# Flex.net
KiCad netlist of a schematic drawn in Altium Designer
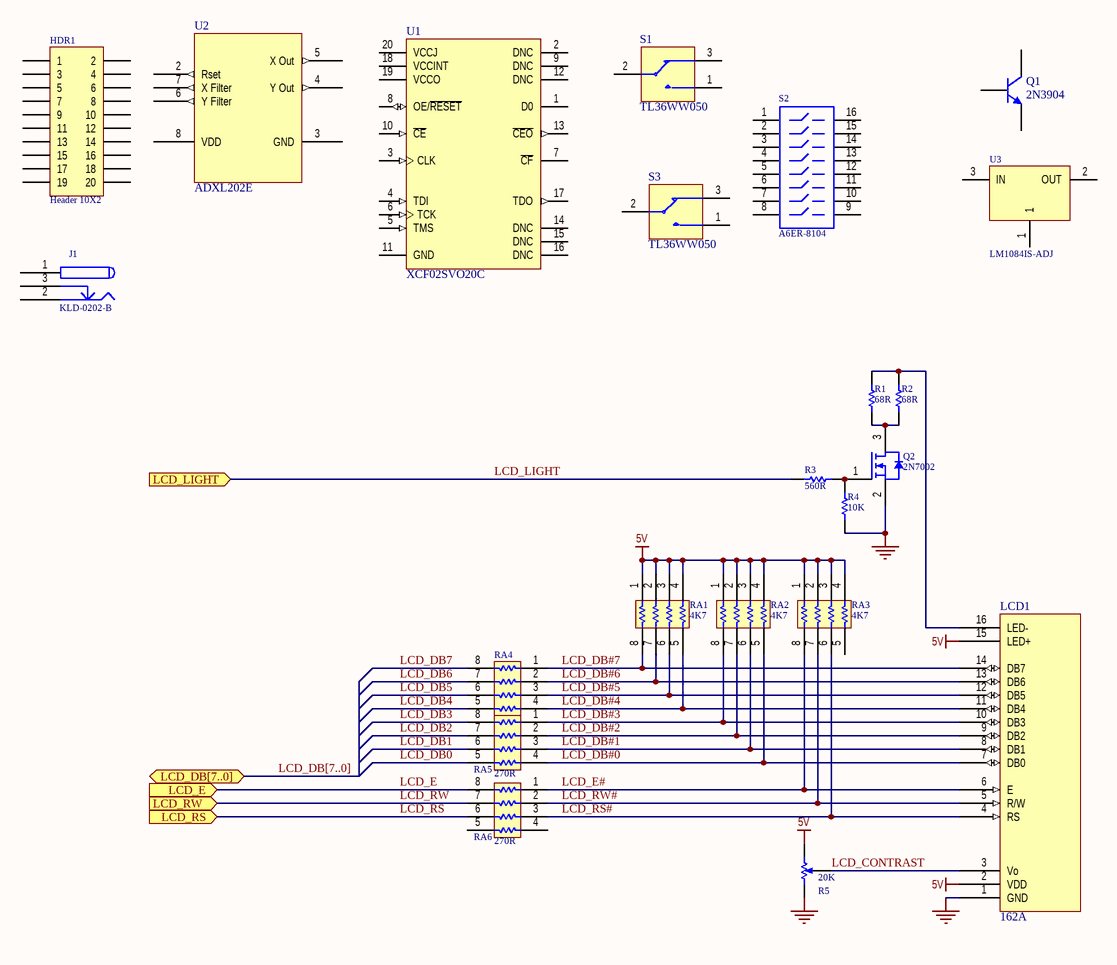
[diagram p0: Flex.SchDoc]

(export (version "E")
  (design (tool "Eeschema 10.0.6"))
  (components
    (comp (ref "HDR1")
      (value "Header 10X2")
      (footprint "HDR2X10")
      (description "Header, 10-Pin, Dual row")
      (libsource (lib "Flex") (part "Header 10X2"))
    )
    (comp (ref "J1")
      (value "KLD-0202-B")
      (footprint "KLD-0202")
      (description "Low Voltage Power Supply Connector")
      (fields (field (name "MANUFACTURER") "Kycon"))
      (libsource (lib "Flex") (part "KLD-0202-B"))
    )
    (comp (ref "LCD1")
      (value "162A")
      (footprint "162A")
      (description "16 char * 2 line LCD character display with b/light")
      (libsource (lib "Flex") (part "162A"))
    )
    (comp (ref "Q1")
      (value "2N3904")
      (footprint "TO-92A")
      (description "NPN General Purpose Amplifier")
      (fields (field (name "PUBLISHER") "Altium Limited"))
      (libsource (lib "Miscellaneous Devices") (part "2N3904"))
    )
    (comp (ref "Q2")
      (value "2N7002")
      (footprint "SO-G3")
      (description "N Channel Mosfet")
      (libsource (lib "Flex") (part "2N7002"))
    )
    (comp (ref "R1")
      (value "68R")
      (footprint "CC2012-0805")
      (description "Resistor")
      (libsource (lib "Flex") (part "RES_2"))
    )
    (comp (ref "R2")
      (value "68R")
      (footprint "CC2012-0805")
      (description "Resistor")
      (libsource (lib "Flex") (part "RES_2"))
    )
    (comp (ref "R3")
      (value "560R")
      (footprint "CC2012-0805")
      (description "Resistor")
      (libsource (lib "SpiritLevel_2E") (part "RES"))
    )
    (comp (ref "R4")
      (value "10K")
      (footprint "CR2012-0805")
      (description "Resistor")
      (libsource (lib "Flex") (part "RES"))
    )
    (comp (ref "R5")
      (value "20K")
      (footprint "POT4MM-2")
      (description "Square Trimming Potentiometer")
      (libsource (lib "Flex") (part "RPot SM"))
    )
    (comp (ref "RA1")
      (value "4K7")
      (footprint "MNR34T")
      (description "3216x4 Resistor Array")
      (libsource (lib "Flex") (part "MNR34"))
    )
    (comp (ref "RA2")
      (value "4K7")
      (footprint "MNR34T")
      (description "3216x4 Resistor Array")
      (libsource (lib "Flex") (part "MNR34"))
    )
    (comp (ref "RA3")
      (value "4K7")
      (footprint "MNR34T")
      (description "3216x4 Resistor Array")
      (libsource (lib "Flex") (part "MNR34"))
    )
    (comp (ref "RA4")
      (value "270R")
      (footprint "MNR34")
      (description "3216x4 Resistor Array")
      (libsource (lib "") (part "MNR34_1"))
    )
    (comp (ref "RA5")
      (value "270R")
      (footprint "MNR34")
      (description "3216x4 Resistor Array")
      (libsource (lib "") (part "MNR34_1"))
    )
    (comp (ref "RA6")
      (value "270R")
      (footprint "MNR34")
      (description "3216x4 Resistor Array")
      (libsource (lib "") (part "MNR34_1"))
    )
    (comp (ref "S1")
      (value "TL36WW050")
      (footprint "PCB_SWITCH")
      (description "SPDT Subminiature Toggle Switch")
      (libsource (lib "Flex") (part "PCB_MOUNT_SWITCH"))
    )
    (comp (ref "S2")
      (value "A6ER-8104")
      (footprint "DIP-16-KEY")
      (description "DIP Switch Side actuator long liver Piano Key")
      (libsource (lib "Flex") (part "A6ER-8104"))
    )
    (comp (ref "S3")
      (value "TL36WW050")
      (footprint "PCB_SWITCH")
      (description "SPDT Subminiature Toggle Switch")
      (libsource (lib "Flex") (part "PCB_MOUNT_SWITCH"))
    )
    (comp (ref "U1") (value "XCF02SVO20C") (footprint "VO20") (libsource (lib "Flex") (part "XCF02SVO20C")))
    (comp (ref "U2")
      (value "ADXL202E")
      (footprint "E-8")
      (description "Accelerometer with Digital Output")
      (libsource (lib "Flex") (part "ADXL202E"))
    )
    (comp (ref "U3")
      (value "LM1084IS-ADJ")
      (footprint "TO-263")
      (description "5A Low Dropout Possitive Regulators")
      (libsource (lib "Flex") (part "LM1084IS-ADJ"))
    )
  )
  (nets
    (net (code "1") (name "/LCD_CONTRAST") (class "Default")
      (node (ref "LCD1") (pin "3") (pinfunction "Vo_3") (pintype "tri_state"))
      (node (ref "R5") (pin "W") (pintype "passive"))
    )
    (net (code "2") (name "/LCD_DB#0") (class "Default")
      (node (ref "LCD1") (pin "7") (pinfunction "DB0_7") (pintype "bidirectional"))
      (node (ref "RA2") (pin "5") (pintype "passive"))
      (node (ref "RA5") (pin "4") (pintype "passive"))
    )
    (net (code "3") (name "/LCD_DB#1") (class "Default")
      (node (ref "LCD1") (pin "8") (pinfunction "DB1_8") (pintype "bidirectional"))
      (node (ref "RA2") (pin "6") (pintype "passive"))
      (node (ref "RA5") (pin "3") (pintype "passive"))
    )
    (net (code "4") (name "/LCD_DB#2") (class "Default")
      (node (ref "LCD1") (pin "9") (pinfunction "DB2_9") (pintype "bidirectional"))
      (node (ref "RA2") (pin "7") (pintype "passive"))
      (node (ref "RA5") (pin "2") (pintype "passive"))
    )
    (net (code "5") (name "/LCD_DB#3") (class "Default")
      (node (ref "LCD1") (pin "10") (pinfunction "DB3_10") (pintype "bidirectional"))
      (node (ref "RA2") (pin "8") (pintype "passive"))
      (node (ref "RA5") (pin "1") (pintype "passive"))
    )
    (net (code "6") (name "/LCD_DB#4") (class "Default")
      (node (ref "LCD1") (pin "11") (pinfunction "DB4_11") (pintype "bidirectional"))
      (node (ref "RA1") (pin "5") (pintype "passive"))
      (node (ref "RA4") (pin "4") (pintype "passive"))
    )
    (net (code "7") (name "/LCD_DB#5") (class "Default")
      (node (ref "LCD1") (pin "12") (pinfunction "DB5_12") (pintype "bidirectional"))
      (node (ref "RA1") (pin "6") (pintype "passive"))
      (node (ref "RA4") (pin "3") (pintype "passive"))
    )
    (net (code "8") (name "/LCD_DB#6") (class "Default")
      (node (ref "LCD1") (pin "13") (pinfunction "DB6_13") (pintype "bidirectional"))
      (node (ref "RA1") (pin "7") (pintype "passive"))
      (node (ref "RA4") (pin "2") (pintype "passive"))
    )
    (net (code "9") (name "/LCD_DB#7") (class "Default")
      (node (ref "LCD1") (pin "14") (pinfunction "DB7_14") (pintype "bidirectional"))
      (node (ref "RA1") (pin "8") (pintype "passive"))
      (node (ref "RA4") (pin "1") (pintype "passive"))
    )
    (net (code "10") (name "/LCD_DB0") (class "Default") (node (ref "RA5") (pin "5") (pintype "passive")))
    (net (code "11") (name "/LCD_DB1") (class "Default") (node (ref "RA5") (pin "6") (pintype "passive")))
    (net (code "12") (name "/LCD_DB2") (class "Default") (node (ref "RA5") (pin "7") (pintype "passive")))
    (net (code "13") (name "/LCD_DB3") (class "Default") (node (ref "RA5") (pin "8") (pintype "passive")))
    (net (code "14") (name "/LCD_DB4") (class "Default") (node (ref "RA4") (pin "5") (pintype "passive")))
    (net (code "15") (name "/LCD_DB5") (class "Default") (node (ref "RA4") (pin "6") (pintype "passive")))
    (net (code "16") (name "/LCD_DB6") (class "Default") (node (ref "RA4") (pin "7") (pintype "passive")))
    (net (code "17") (name "/LCD_DB7") (class "Default") (node (ref "RA4") (pin "8") (pintype "passive")))
    (net (code "19") (name "/LCD_E") (class "Default") (node (ref "RA6") (pin "8") (pintype "passive")))
    (net (code "20") (name "/LCD_E#") (class "Default")
      (node (ref "LCD1") (pin "6") (pinfunction "E_6") (pintype "input"))
      (node (ref "RA3") (pin "8") (pintype "passive"))
      (node (ref "RA6") (pin "1") (pintype "passive"))
    )
    (net (code "21") (name "/LCD_LIGHT") (class "Default")
      (node (ref "R3") (pin "1") (pinfunction "1_1") (pintype "passive"))
    )
    (net (code "22") (name "/LCD_RS") (class "Default") (node (ref "RA6") (pin "6") (pintype "passive")))
    (net (code "23") (name "/LCD_RS#") (class "Default")
      (node (ref "LCD1") (pin "4") (pinfunction "RS_4") (pintype "input"))
      (node (ref "RA3") (pin "6") (pintype "passive"))
      (node (ref "RA6") (pin "3") (pintype "passive"))
    )
    (net (code "24") (name "/LCD_RW") (class "Default") (node (ref "RA6") (pin "7") (pintype "passive")))
    (net (code "25") (name "/LCD_RW#") (class "Default")
      (node (ref "LCD1") (pin "5") (pinfunction "R/W_5") (pintype "input"))
      (node (ref "RA3") (pin "7") (pintype "passive"))
      (node (ref "RA6") (pin "2") (pintype "passive"))
    )
    (net (code "26") (name "5V") (class "Default")
      (node (ref "LCD1") (pin "15") (pinfunction "LED+_15") (pintype "power_in"))
      (node (ref "LCD1") (pin "2") (pinfunction "VDD_2") (pintype "power_in"))
      (node (ref "R5") (pin "CW") (pinfunction "+_CW") (pintype "passive"))
      (node (ref "RA1") (pin "1") (pintype "passive"))
      (node (ref "RA1") (pin "2") (pintype "passive"))
      (node (ref "RA1") (pin "3") (pintype "passive"))
      (node (ref "RA1") (pin "4") (pintype "passive"))
      (node (ref "RA2") (pin "1") (pintype "passive"))
      (node (ref "RA2") (pin "2") (pintype "passive"))
      (node (ref "RA2") (pin "3") (pintype "passive"))
      (node (ref "RA2") (pin "4") (pintype "passive"))
      (node (ref "RA3") (pin "1") (pintype "passive"))
      (node (ref "RA3") (pin "2") (pintype "passive"))
      (node (ref "RA3") (pin "3") (pintype "passive"))
      (node (ref "RA3") (pin "4") (pintype "passive"))
    )
    (net (code "27") (name "GND") (class "Default")
      (node (ref "LCD1") (pin "1") (pinfunction "GND_1") (pintype "power_in"))
      (node (ref "Q2") (pin "2") (pintype "passive"))
      (node (ref "R4") (pin "1") (pinfunction "1_1") (pintype "passive"))
      (node (ref "R5") (pin "CCW") (pinfunction "-_CCW") (pintype "passive"))
    )
    (net (code "28") (name "Net-(LCD1-LED-)") (class "Default")
      (node (ref "LCD1") (pin "16") (pinfunction "LED-_16") (pintype "power_in"))
      (node (ref "R1") (pin "1") (pinfunction "1_1") (pintype "passive"))
      (node (ref "R2") (pin "1") (pinfunction "1_1") (pintype "passive"))
    )
    (net (code "29") (name "Net-(Q2-Pad1)") (class "Default")
      (node (ref "Q2") (pin "1") (pintype "passive"))
      (node (ref "R3") (pin "2") (pinfunction "2_2") (pintype "passive"))
      (node (ref "R4") (pin "2") (pinfunction "2_2") (pintype "passive"))
    )
    (net (code "30") (name "Net-(Q2-Pad3)") (class "Default")
      (node (ref "Q2") (pin "3") (pintype "passive"))
      (node (ref "R1") (pin "2") (pinfunction "2_2") (pintype "passive"))
      (node (ref "R2") (pin "2") (pinfunction "2_2") (pintype "passive"))
    )
    (net (code "31") (name "unconnected-(HDR1-Pad1)") (class "Default")
      (node (ref "HDR1") (pin "1") (pinfunction "1_1") (pintype "passive"))
    )
    (net (code "32") (name "unconnected-(HDR1-Pad2)") (class "Default")
      (node (ref "HDR1") (pin "2") (pinfunction "2_2") (pintype "passive"))
    )
    (net (code "33") (name "unconnected-(HDR1-Pad3)") (class "Default")
      (node (ref "HDR1") (pin "3") (pinfunction "3_3") (pintype "passive"))
    )
    (net (code "34") (name "unconnected-(HDR1-Pad4)") (class "Default")
      (node (ref "HDR1") (pin "4") (pinfunction "4_4") (pintype "passive"))
    )
    (net (code "35") (name "unconnected-(HDR1-Pad5)") (class "Default")
      (node (ref "HDR1") (pin "5") (pinfunction "5_5") (pintype "passive"))
    )
    (net (code "36") (name "unconnected-(HDR1-Pad6)") (class "Default")
      (node (ref "HDR1") (pin "6") (pinfunction "6_6") (pintype "passive"))
    )
    (net (code "37") (name "unconnected-(HDR1-Pad7)") (class "Default")
      (node (ref "HDR1") (pin "7") (pinfunction "7_7") (pintype "passive"))
    )
    (net (code "38") (name "unconnected-(HDR1-Pad8)") (class "Default")
      (node (ref "HDR1") (pin "8") (pinfunction "8_8") (pintype "passive"))
    )
    (net (code "39") (name "unconnected-(HDR1-Pad9)") (class "Default")
      (node (ref "HDR1") (pin "9") (pinfunction "9_9") (pintype "passive"))
    )
    (net (code "40") (name "unconnected-(HDR1-Pad10)") (class "Default")
      (node (ref "HDR1") (pin "10") (pinfunction "10_10") (pintype "passive"))
    )
    (net (code "41") (name "unconnected-(HDR1-Pad11)") (class "Default")
      (node (ref "HDR1") (pin "11") (pinfunction "11_11") (pintype "passive"))
    )
    (net (code "42") (name "unconnected-(HDR1-Pad12)") (class "Default")
      (node (ref "HDR1") (pin "12") (pinfunction "12_12") (pintype "passive"))
    )
    (net (code "43") (name "unconnected-(HDR1-Pad13)") (class "Default")
      (node (ref "HDR1") (pin "13") (pinfunction "13_13") (pintype "passive"))
    )
    (net (code "44") (name "unconnected-(HDR1-Pad14)") (class "Default")
      (node (ref "HDR1") (pin "14") (pinfunction "14_14") (pintype "passive"))
    )
    (net (code "45") (name "unconnected-(HDR1-Pad15)") (class "Default")
      (node (ref "HDR1") (pin "15") (pinfunction "15_15") (pintype "passive"))
    )
    (net (code "46") (name "unconnected-(HDR1-Pad16)") (class "Default")
      (node (ref "HDR1") (pin "16") (pinfunction "16_16") (pintype "passive"))
    )
    (net (code "47") (name "unconnected-(HDR1-Pad17)") (class "Default")
      (node (ref "HDR1") (pin "17") (pinfunction "17_17") (pintype "passive"))
    )
    (net (code "48") (name "unconnected-(HDR1-Pad18)") (class "Default")
      (node (ref "HDR1") (pin "18") (pinfunction "18_18") (pintype "passive"))
    )
    (net (code "49") (name "unconnected-(HDR1-Pad19)") (class "Default")
      (node (ref "HDR1") (pin "19") (pinfunction "19_19") (pintype "passive"))
    )
    (net (code "50") (name "unconnected-(HDR1-Pad20)") (class "Default")
      (node (ref "HDR1") (pin "20") (pinfunction "20_20") (pintype "passive"))
    )
    (net (code "51") (name "unconnected-(J1-Pad1)") (class "Default")
      (node (ref "J1") (pin "1") (pintype "power_in"))
    )
    (net (code "52") (name "unconnected-(J1-Pad2)") (class "Default")
      (node (ref "J1") (pin "2") (pintype "power_in"))
    )
    (net (code "53") (name "unconnected-(J1-Pad3)") (class "Default")
      (node (ref "J1") (pin "3") (pintype "power_in"))
    )
    (net (code "54") (name "unconnected-(Q1-B-Pad2)") (class "Default")
      (node (ref "Q1") (pin "2") (pinfunction "B_2") (pintype "passive"))
    )
    (net (code "55") (name "unconnected-(Q1-C-Pad3)") (class "Default")
      (node (ref "Q1") (pin "3") (pinfunction "C_3") (pintype "passive"))
    )
    (net (code "56") (name "unconnected-(Q1-E-Pad1)") (class "Default")
      (node (ref "Q1") (pin "1") (pinfunction "E_1") (pintype "passive"))
    )
    (net (code "57") (name "unconnected-(RA3-Pad5)") (class "Default")
      (node (ref "RA3") (pin "5") (pintype "passive"))
    )
    (net (code "58") (name "unconnected-(RA6-Pad4)") (class "Default")
      (node (ref "RA6") (pin "4") (pintype "passive"))
    )
    (net (code "59") (name "unconnected-(RA6-Pad5)") (class "Default")
      (node (ref "RA6") (pin "5") (pintype "passive"))
    )
    (net (code "60") (name "unconnected-(S1-Pad1)") (class "Default")
      (node (ref "S1") (pin "1") (pintype "passive"))
    )
    (net (code "61") (name "unconnected-(S1-Pad2)") (class "Default")
      (node (ref "S1") (pin "2") (pintype "passive"))
    )
    (net (code "62") (name "unconnected-(S1-Pad3)") (class "Default")
      (node (ref "S1") (pin "3") (pintype "passive"))
    )
    (net (code "63") (name "unconnected-(S2-Pad1)") (class "Default")
      (node (ref "S2") (pin "1") (pinfunction "1_1") (pintype "passive"))
    )
    (net (code "64") (name "unconnected-(S2-Pad2)") (class "Default")
      (node (ref "S2") (pin "2") (pinfunction "2_2") (pintype "passive"))
    )
    (net (code "65") (name "unconnected-(S2-Pad3)") (class "Default")
      (node (ref "S2") (pin "3") (pinfunction "3_3") (pintype "passive"))
    )
    (net (code "66") (name "unconnected-(S2-Pad4)") (class "Default")
      (node (ref "S2") (pin "4") (pinfunction "4_4") (pintype "passive"))
    )
    (net (code "67") (name "unconnected-(S2-Pad5)") (class "Default")
      (node (ref "S2") (pin "5") (pinfunction "5_5") (pintype "passive"))
    )
    (net (code "68") (name "unconnected-(S2-Pad6)") (class "Default")
      (node (ref "S2") (pin "6") (pinfunction "6_6") (pintype "passive"))
    )
    (net (code "69") (name "unconnected-(S2-Pad7)") (class "Default")
      (node (ref "S2") (pin "7") (pinfunction "7_7") (pintype "passive"))
    )
    (net (code "70") (name "unconnected-(S2-Pad8)") (class "Default")
      (node (ref "S2") (pin "8") (pinfunction "8_8") (pintype "passive"))
    )
    (net (code "71") (name "unconnected-(S2-Pad9)") (class "Default")
      (node (ref "S2") (pin "9") (pinfunction "9_9") (pintype "passive"))
    )
    (net (code "72") (name "unconnected-(S2-Pad10)") (class "Default")
      (node (ref "S2") (pin "10") (pinfunction "10_10") (pintype "passive"))
    )
    (net (code "73") (name "unconnected-(S2-Pad11)") (class "Default")
      (node (ref "S2") (pin "11") (pinfunction "11_11") (pintype "passive"))
    )
    (net (code "74") (name "unconnected-(S2-Pad12)") (class "Default")
      (node (ref "S2") (pin "12") (pinfunction "12_12") (pintype "passive"))
    )
    (net (code "75") (name "unconnected-(S2-Pad13)") (class "Default")
      (node (ref "S2") (pin "13") (pinfunction "13_13") (pintype "passive"))
    )
    (net (code "76") (name "unconnected-(S2-Pad14)") (class "Default")
      (node (ref "S2") (pin "14") (pinfunction "14_14") (pintype "passive"))
    )
    (net (code "77") (name "unconnected-(S2-Pad15)") (class "Default")
      (node (ref "S2") (pin "15") (pinfunction "15_15") (pintype "passive"))
    )
    (net (code "78") (name "unconnected-(S2-Pad16)") (class "Default")
      (node (ref "S2") (pin "16") (pinfunction "16_16") (pintype "passive"))
    )
    (net (code "79") (name "unconnected-(S3-Pad1)") (class "Default")
      (node (ref "S3") (pin "1") (pintype "passive"))
    )
    (net (code "80") (name "unconnected-(S3-Pad2)") (class "Default")
      (node (ref "S3") (pin "2") (pintype "passive"))
    )
    (net (code "81") (name "unconnected-(S3-Pad3)") (class "Default")
      (node (ref "S3") (pin "3") (pintype "passive"))
    )
    (net (code "82") (name "unconnected-(U1-CLK-Pad3)") (class "Default")
      (node (ref "U1") (pin "3") (pinfunction "CLK_3") (pintype "input"))
    )
    (net (code "83") (name "unconnected-(U1-D0-Pad1)") (class "Default")
      (node (ref "U1") (pin "1") (pinfunction "D0_1") (pintype "tri_state"))
    )
    (net (code "84") (name "unconnected-(U1-DNC-Pad2)") (class "Default")
      (node (ref "U1") (pin "2") (pinfunction "DNC_2") (pintype "passive"))
    )
    (net (code "85") (name "unconnected-(U1-DNC-Pad9)") (class "Default")
      (node (ref "U1") (pin "9") (pinfunction "DNC_9") (pintype "passive"))
    )
    (net (code "86") (name "unconnected-(U1-DNC-Pad12)") (class "Default")
      (node (ref "U1") (pin "12") (pinfunction "DNC_12") (pintype "passive"))
    )
    (net (code "87") (name "unconnected-(U1-DNC-Pad14)") (class "Default")
      (node (ref "U1") (pin "14") (pinfunction "DNC_14") (pintype "passive"))
    )
    (net (code "88") (name "unconnected-(U1-DNC-Pad15)") (class "Default")
      (node (ref "U1") (pin "15") (pinfunction "DNC_15") (pintype "passive"))
    )
    (net (code "89") (name "unconnected-(U1-DNC-Pad16)") (class "Default")
      (node (ref "U1") (pin "16") (pinfunction "DNC_16") (pintype "passive"))
    )
    (net (code "90") (name "unconnected-(U1-GND-Pad11)") (class "Default")
      (node (ref "U1") (pin "11") (pinfunction "GND_11") (pintype "power_in"))
    )
    (net (code "91") (name "unconnected-(U1-OE{slash}~{RESET}-Pad8)") (class "Default")
      (node (ref "U1") (pin "8") (pinfunction "OE/~{RESET}_8") (pintype "bidirectional"))
    )
    (net (code "92") (name "unconnected-(U1-TCK-Pad6)") (class "Default")
      (node (ref "U1") (pin "6") (pinfunction "TCK_6") (pintype "input"))
    )
    (net (code "93") (name "unconnected-(U1-TDI-Pad4)") (class "Default")
      (node (ref "U1") (pin "4") (pinfunction "TDI_4") (pintype "input"))
    )
    (net (code "94") (name "unconnected-(U1-TDO-Pad17)") (class "Default")
      (node (ref "U1") (pin "17") (pinfunction "TDO_17") (pintype "output"))
    )
    (net (code "95") (name "unconnected-(U1-TMS-Pad5)") (class "Default")
      (node (ref "U1") (pin "5") (pinfunction "TMS_5") (pintype "input"))
    )
    (net (code "96") (name "unconnected-(U1-VCCINT-Pad18)") (class "Default")
      (node (ref "U1") (pin "18") (pinfunction "VCCINT_18") (pintype "power_in"))
    )
    (net (code "97") (name "unconnected-(U1-VCCJ-Pad20)") (class "Default")
      (node (ref "U1") (pin "20") (pinfunction "VCCJ_20") (pintype "power_in"))
    )
    (net (code "98") (name "unconnected-(U1-VCCO-Pad19)") (class "Default")
      (node (ref "U1") (pin "19") (pinfunction "VCCO_19") (pintype "power_in"))
    )
    (net (code "99") (name "unconnected-(U1-~{CEO}-Pad13)") (class "Default")
      (node (ref "U1") (pin "13") (pinfunction "~{CEO}_13") (pintype "output"))
    )
    (net (code "100") (name "unconnected-(U1-~{CE}-Pad10)") (class "Default")
      (node (ref "U1") (pin "10") (pinfunction "~{CE}_10") (pintype "input"))
    )
    (net (code "101") (name "unconnected-(U1-~{CF}-Pad7)") (class "Default")
      (node (ref "U1") (pin "7") (pinfunction "~{CF}_7") (pintype "open_collector"))
    )
    (net (code "102") (name "unconnected-(U2-GND-Pad3)") (class "Default")
      (node (ref "U2") (pin "3") (pinfunction "GND_3") (pintype "power_in"))
    )
    (net (code "103") (name "unconnected-(U2-Rset-Pad2)") (class "Default")
      (node (ref "U2") (pin "2") (pinfunction "Rset_2") (pintype "output"))
    )
    (net (code "104") (name "unconnected-(U2-Self_Test-Pad1)") (class "Default")
      (node (ref "U2") (pin "1") (pinfunction "Self_Test_1") (pintype "input"))
    )
    (net (code "105") (name "unconnected-(U2-VDD-Pad8)") (class "Default")
      (node (ref "U2") (pin "8") (pinfunction "VDD_8") (pintype "power_in"))
    )
    (net (code "106") (name "unconnected-(U2-X_Filter-Pad7)") (class "Default")
      (node (ref "U2") (pin "7") (pinfunction "X_Filter_7") (pintype "output"))
    )
    (net (code "107") (name "unconnected-(U2-X_Out-Pad5)") (class "Default")
      (node (ref "U2") (pin "5") (pinfunction "X_Out_5") (pintype "output"))
    )
    (net (code "108") (name "unconnected-(U2-Y_Filter-Pad6)") (class "Default")
      (node (ref "U2") (pin "6") (pinfunction "Y_Filter_6") (pintype "output"))
    )
    (net (code "109") (name "unconnected-(U2-Y_Out-Pad4)") (class "Default")
      (node (ref "U2") (pin "4") (pinfunction "Y_Out_4") (pintype "output"))
    )
    (net (code "110") (name "unconnected-(U3-IN-Pad3)") (class "Default")
      (node (ref "U3") (pin "3") (pinfunction "IN_3") (pintype "power_in"))
    )
    (net (code "111") (name "unconnected-(U3-OUT-Pad2)") (class "Default")
      (node (ref "U3") (pin "2") (pinfunction "OUT_2") (pintype "power_in"))
    )
    (net (code "112") (name "unconnected-(U3-Pad1)") (class "Default")
      (node (ref "U3") (pin "1") (pinfunction "1_1") (pintype "passive"))
    )
  )
)
